# Power.net
KiCad netlist of a schematic drawn in Altium Designer
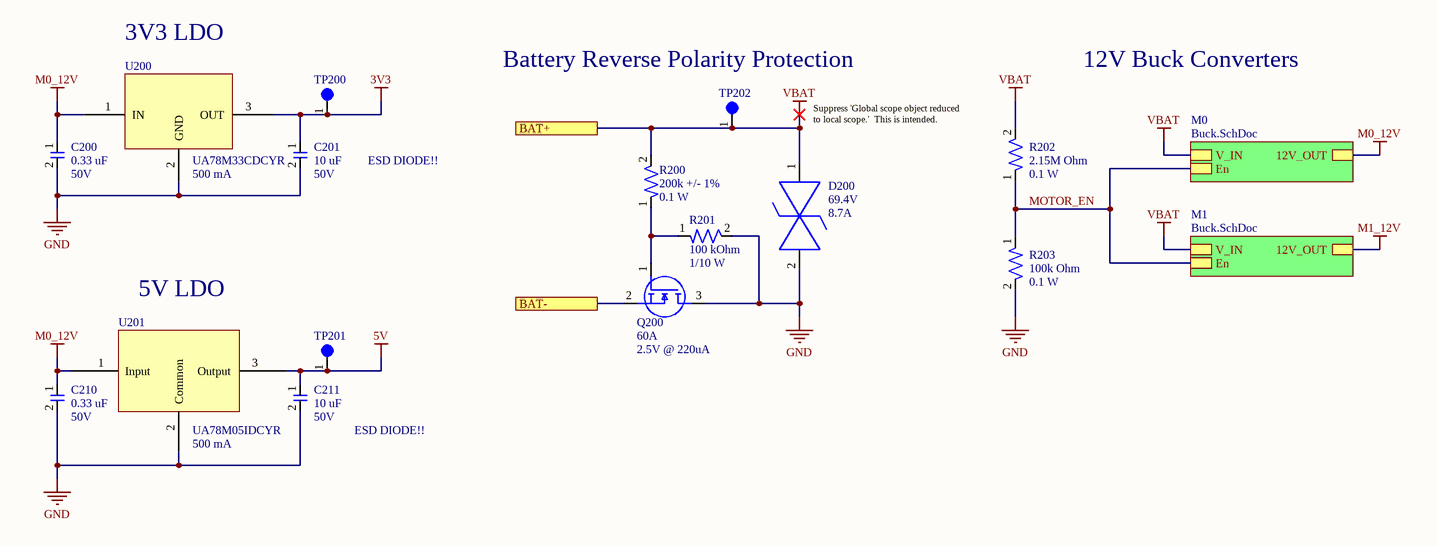
[diagram p0: Power.SchDoc]

(export (version "E")
  (design (tool "Eeschema 10.0.6"))
  (components
    (comp (ref "C200")
      (value "CGA3E3X7R1H334K080AB")
      (footprint "MasterLib:CAP-0603")
      (description "0.33 µF ±10% 50V Ceramic Capacitor X7R 0603 (1608 Metric)")
      (fields
        (field (name "MANUFACTURER") "TDK Corporation")
        (field (name "TOLERANCE") "10%")
        (field (name "CAPACITANCE") "0.33 uF")
        (field (name "VOLTAGE") "50V")
      )
      (libsource (lib "MasterLib") (part "CAP-0.33uF-0001"))
    )
    (comp (ref "C201")
      (value "CL31B106KBHNNNE")
      (footprint "MasterLib:CAP-1206")
      (description "10 µF ±10% 50V Ceramic Capacitor X7R 1206 (3216 Metric)")
      (fields
        (field (name "MANUFACTURER") "Samsung Electro-Mechanics")
        (field (name "CAPACITANCE") "10 uF")
        (field (name "VOLTAGE RATING") "50V")
        (field (name "TOLERANCE") "10%")
      )
      (libsource (lib "MasterLib") (part "CAP-10U-0001"))
    )
    (comp (ref "C210")
      (value "CGA3E3X7R1H334K080AB")
      (footprint "MasterLib:CAP-0603")
      (description "0.33 µF ±10% 50V Ceramic Capacitor X7R 0603 (1608 Metric)")
      (fields
        (field (name "MANUFACTURER") "TDK Corporation")
        (field (name "TOLERANCE") "10%")
        (field (name "CAPACITANCE") "0.33 uF")
        (field (name "VOLTAGE") "50V")
      )
      (libsource (lib "MasterLib") (part "CAP-0.33uF-0001"))
    )
    (comp (ref "C211")
      (value "CL31B106KBHNNNE")
      (footprint "MasterLib:CAP-1206")
      (description "10 µF ±10% 50V Ceramic Capacitor X7R 1206 (3216 Metric)")
      (fields
        (field (name "MANUFACTURER") "Samsung Electro-Mechanics")
        (field (name "CAPACITANCE") "10 uF")
        (field (name "VOLTAGE RATING") "50V")
        (field (name "TOLERANCE") "10%")
      )
      (libsource (lib "MasterLib") (part "CAP-10U-0001"))
    )
    (comp (ref "D200")
      (value "SMBJE43CAH")
      (footprint "MasterLib:DO-214AA (SMBJ)")
      (description "69.4V Clamp 8.7A Ipp Tvs Diode Surface Mount DO-214AA (SMBJ)")
      (fields (field (name "VCLAMP") "69.4V") (field (name "PEAK PULSER CURRENT") "8.7A"))
      (libsource (lib "MasterLib") (part "DIO-69.4V-0001"))
    )
    (comp (ref "Q200")
      (value "TPH7R006PL,L1Q")
      (footprint "MasterLib:NMOS-8PowerVDFN")
      (description "N-Channel 60 V 60A (Tc) 81W (Tc) Surface Mount 8-SOP Advance (5x5)")
      (fields (field (name "DRAIN CURRENT") "60A") (field (name "VGS") "2.5V @ 220uA"))
      (libsource (lib "MasterLib") (part "NMOS-60A-0001"))
    )
    (comp (ref "R200")
      (value "ERJ-3EKF2003V")
      (footprint "MasterLib:RES-0603")
      (description "200 kOhms ±1% 0.1W, 1/10W Chip Resistor 0603 (1608 Metric) Automotive AEC-Q200 Thick Film")
      (fields
        (field (name "MANUFACTURER") "Panasonic Electronic Components")
        (field (name "RESISTANCE") "200k +/- 1%")
        (field (name "POWER RATING") "0.1 W")
      )
      (libsource (lib "MasterLib") (part "RES-200K-0001"))
    )
    (comp (ref "R201")
      (value "RC0603FR-07100KL")
      (footprint "MasterLib:RES-0603")
      (description "100 kOhms ±1% 0.1W, 1/10W Chip Resistor 0603 (1608 Metric) Moisture Resistant Thick Film")
      (fields
        (field (name "TOLERANCE") "+/- 1%")
        (field (name "RESISTANCE") "100 kOhm")
        (field (name "POWER") "1/10 W")
      )
      (libsource (lib "MasterLib") (part "RES-100K-0003"))
    )
    (comp (ref "R202")
      (value "RC0603FR-072M15L")
      (footprint "MasterLib:RES-0603")
      (description "2.15 MOhms ±1% 0.1W, 1/10W Chip Resistor 0603 (1608 Metric) Moisture Resistant Thick Film")
      (fields
        (field (name "TOLERANCE") "1%")
        (field (name "RESISTANCE") "2.15M Ohm")
        (field (name "POWER") "0.1 W")
      )
      (libsource (lib "MasterLib") (part "RES-2.15M-0001"))
    )
    (comp (ref "R203")
      (value "RC0603FR-07100KL")
      (footprint "MasterLib:RES-0603")
      (description "100 kOhms ±1% 0.1W, 1/10W Chip Resistor 0603 (1608 Metric) Moisture Resistant Thick Film")
      (fields
        (field (name "TOLERANCE") "1%")
        (field (name "RESISTANCE") "100k Ohm")
        (field (name "POWER") "0.1 W")
      )
      (libsource (lib "MasterLib") (part "RES-100K-0003"))
    )
    (comp (ref "TP200")
      (value "5003")
      (footprint "MasterLib:TEST-POINT-0001")
      (description "Oranange PC Test Point, Miniature Phoisphor Bronze Silver Plating Through Hole Mounting Type")
      (libsource (lib "MasterLib") (part "TEST-POINT-0001"))
    )
    (comp (ref "TP201")
      (value "5003")
      (footprint "MasterLib:TEST-POINT-0001")
      (description "Oranange PC Test Point, Miniature Phoisphor Bronze Silver Plating Through Hole Mounting Type")
      (libsource (lib "MasterLib") (part "TEST-POINT-0001"))
    )
    (comp (ref "TP202")
      (value "5003")
      (footprint "MasterLib:TEST-POINT-0001")
      (description "Oranange PC Test Point, Miniature Phoisphor Bronze Silver Plating Through Hole Mounting Type")
      (libsource (lib "MasterLib") (part "TEST-POINT-0001"))
    )
    (comp (ref "U200")
      (value "UA78M33CDCYR")
      (footprint "MasterLib:IC-SOT-223-4")
      (description "Linear Voltage Regulator IC Positive Fixed 1 Output 500mA SOT-223-4")
      (fields (field (name "CURRENT") "500 mA"))
      (libsource (lib "MasterLib") (part "IC-LDO-3.3V-0002"))
    )
    (comp (ref "U201")
      (value "UA78M05IDCYR")
      (footprint "MasterLib:IC-SOT-223-4")
      (description "Linear Voltage Regulator IC Positive Fixed 1 Output 500mA SOT-223-4")
      (fields (field (name "MANUFACTURER") "Texas Instruments") (field (name "CURRENT") "500 mA"))
      (libsource (lib "MasterLib") (part "IC-LDO-5V-0003"))
    )
  )
  (nets
    (net (code "1") (name "/BAT-") (class "Default")
      (node (ref "Q200") (pin "2") (pinfunction "S_2") (pintype "passive"))
    )
    (net (code "2") (name "/MOTOR_EN") (class "Default")
      (node (ref "R202") (pin "1") (pinfunction "1_1") (pintype "passive"))
      (node (ref "R203") (pin "1") (pinfunction "1_1") (pintype "passive"))
    )
    (net (code "3") (name "3V3") (class "Default")
      (node (ref "C201") (pin "1") (pinfunction "1_1") (pintype "passive"))
      (node (ref "TP200") (pin "1") (pinfunction "0_1") (pintype "passive"))
      (node (ref "U200") (pin "3") (pinfunction "OUT_3") (pintype "power_in"))
    )
    (net (code "4") (name "5V") (class "Default")
      (node (ref "C211") (pin "1") (pinfunction "1_1") (pintype "passive"))
      (node (ref "TP201") (pin "1") (pinfunction "0_1") (pintype "passive"))
      (node (ref "U201") (pin "3") (pinfunction "Output_3") (pintype "power_in"))
    )
    (net (code "5") (name "GND") (class "Default")
      (node (ref "C200") (pin "2") (pinfunction "2_2") (pintype "passive"))
      (node (ref "C201") (pin "2") (pinfunction "2_2") (pintype "passive"))
      (node (ref "C210") (pin "2") (pinfunction "2_2") (pintype "passive"))
      (node (ref "C211") (pin "2") (pinfunction "2_2") (pintype "passive"))
      (node (ref "D200") (pin "2") (pintype "passive"))
      (node (ref "Q200") (pin "3") (pinfunction "D_3") (pintype "passive"))
      (node (ref "R201") (pin "2") (pinfunction "2_2") (pintype "passive"))
      (node (ref "R203") (pin "2") (pinfunction "2_2") (pintype "passive"))
      (node (ref "U200") (pin "2") (pinfunction "GND_2") (pintype "power_in"))
      (node (ref "U201") (pin "2") (pinfunction "Common_2") (pintype "power_in"))
    )
    (net (code "6") (name "M0_12V") (class "Default")
      (node (ref "C200") (pin "1") (pinfunction "1_1") (pintype "passive"))
      (node (ref "C210") (pin "1") (pinfunction "1_1") (pintype "passive"))
      (node (ref "U200") (pin "1") (pinfunction "IN_1") (pintype "power_in"))
      (node (ref "U201") (pin "1") (pinfunction "Input_1") (pintype "power_in"))
    )
    (net (code "8") (name "Net-(Q200-G)") (class "Default")
      (node (ref "Q200") (pin "1") (pinfunction "G_1") (pintype "passive"))
      (node (ref "R200") (pin "1") (pinfunction "1_1") (pintype "passive"))
      (node (ref "R201") (pin "1") (pinfunction "1_1") (pintype "passive"))
    )
    (net (code "9") (name "VBAT") (class "Default")
      (node (ref "D200") (pin "1") (pintype "passive"))
      (node (ref "R200") (pin "2") (pinfunction "2_2") (pintype "passive"))
      (node (ref "R202") (pin "2") (pinfunction "2_2") (pintype "passive"))
      (node (ref "TP202") (pin "1") (pinfunction "0_1") (pintype "passive"))
    )
  )
)
